# trill-bar.net
KiCad netlist of a schematic drawn in EAGLE
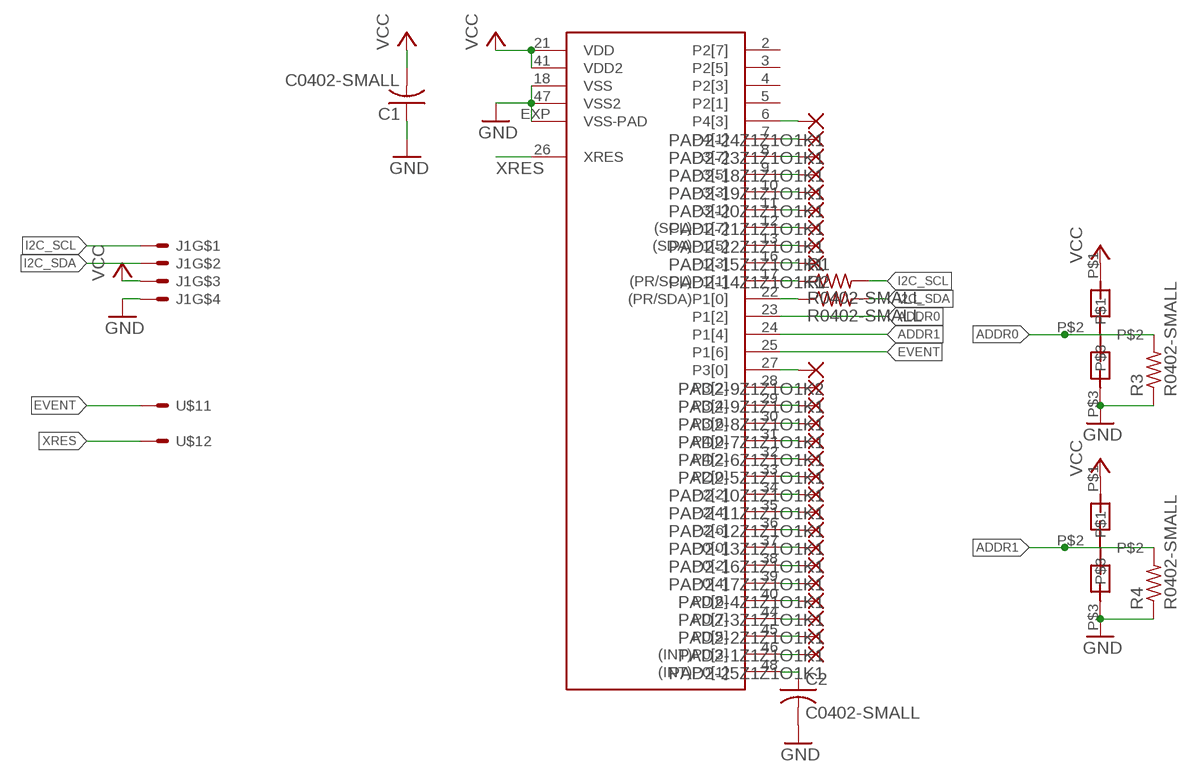
[diagram p0: schematic, sheet 1]

(export (version "E")
  (design (tool "Eeschema 10.0.6"))
  (components
    (comp (ref "C1")
      (value "C0402-SMALL")
      (footprint "eagle-import:C0402-SMALL")
      (libsource (lib "eagle-import") (part "C0402-SMALL"))
    )
    (comp (ref "C2")
      (value "C0402-SMALL")
      (footprint "eagle-import:C0402-SMALL")
      (libsource (lib "eagle-import") (part "C0402-SMALL"))
    )
    (comp (ref "IC1")
      (value "CY8C206X6A")
      (footprint "eagle-import:QFN48-LEADS")
      (libsource (lib "eagle-import") (part "CY8C206X6A"))
    )
    (comp (ref "J1")
      (value "GROVE-SMT")
      (footprint "eagle-import:JST-PH-4-SMT")
      (libsource (lib "eagle-import") (part "GROVE-SMT"))
    )
    (comp (ref "PAD2-1Z1Z1O1K1")
      (value "SMD2")
      (footprint "eagle-import:SMD1,27-2,54")
      (libsource (lib "eagle-import") (part "SMD2"))
    )
    (comp (ref "PAD2-2Z1Z1O1K1")
      (value "SMD2")
      (footprint "eagle-import:SMD1,27-2,54")
      (libsource (lib "eagle-import") (part "SMD2"))
    )
    (comp (ref "PAD2-3Z1Z1O1K1")
      (value "SMD2")
      (footprint "eagle-import:SMD1,27-2,54")
      (libsource (lib "eagle-import") (part "SMD2"))
    )
    (comp (ref "PAD2-4Z1Z1O1K1")
      (value "SMD2")
      (footprint "eagle-import:SMD1,27-2,54")
      (libsource (lib "eagle-import") (part "SMD2"))
    )
    (comp (ref "PAD2-5Z1Z1O1K1")
      (value "SMD2")
      (footprint "eagle-import:SMD1,27-2,54")
      (libsource (lib "eagle-import") (part "SMD2"))
    )
    (comp (ref "PAD2-6Z1Z1O1K1")
      (value "SMD2")
      (footprint "eagle-import:SMD1,27-2,54")
      (libsource (lib "eagle-import") (part "SMD2"))
    )
    (comp (ref "PAD2-7Z1Z1O1K1")
      (value "SMD2")
      (footprint "eagle-import:SMD1,27-2,54")
      (libsource (lib "eagle-import") (part "SMD2"))
    )
    (comp (ref "PAD2-8Z1Z1O1K1")
      (value "SMD2")
      (footprint "eagle-import:SMD1,27-2,54")
      (libsource (lib "eagle-import") (part "SMD2"))
    )
    (comp (ref "PAD2-9Z1Z1O1K1")
      (value "SMD2")
      (footprint "eagle-import:SMD1,27-2,54")
      (libsource (lib "eagle-import") (part "SMD2"))
    )
    (comp (ref "PAD2-9Z1Z1O1K2")
      (value "SMD2")
      (footprint "eagle-import:SMD1,27-2,54")
      (libsource (lib "eagle-import") (part "SMD2"))
    )
    (comp (ref "PAD2-10Z1Z1O1K1")
      (value "SMD2")
      (footprint "eagle-import:SMD1,27-2,54")
      (libsource (lib "eagle-import") (part "SMD2"))
    )
    (comp (ref "PAD2-11Z1Z1O1K1")
      (value "SMD2")
      (footprint "eagle-import:SMD1,27-2,54")
      (libsource (lib "eagle-import") (part "SMD2"))
    )
    (comp (ref "PAD2-12Z1Z1O1K1")
      (value "SMD2")
      (footprint "eagle-import:SMD1,27-2,54")
      (libsource (lib "eagle-import") (part "SMD2"))
    )
    (comp (ref "PAD2-13Z1Z1O1K1")
      (value "SMD2")
      (footprint "eagle-import:SMD1,27-2,54")
      (libsource (lib "eagle-import") (part "SMD2"))
    )
    (comp (ref "PAD2-14Z1Z1O1K1")
      (value "SMD2")
      (footprint "eagle-import:SMD1,27-2,54")
      (libsource (lib "eagle-import") (part "SMD2"))
    )
    (comp (ref "PAD2-15Z1Z1O1K1")
      (value "SMD2")
      (footprint "eagle-import:SMD1,27-2,54")
      (libsource (lib "eagle-import") (part "SMD2"))
    )
    (comp (ref "PAD2-16Z1Z1O1K1")
      (value "SMD2")
      (footprint "eagle-import:SMD1,27-2,54")
      (libsource (lib "eagle-import") (part "SMD2"))
    )
    (comp (ref "PAD2-17Z1Z1O1K1")
      (value "SMD2")
      (footprint "eagle-import:SMD1,27-2,54")
      (libsource (lib "eagle-import") (part "SMD2"))
    )
    (comp (ref "PAD2-18Z1Z1O1K1")
      (value "SMD2")
      (footprint "eagle-import:SMD1,27-2,54")
      (libsource (lib "eagle-import") (part "SMD2"))
    )
    (comp (ref "PAD2-19Z1Z1O1K1")
      (value "SMD2")
      (footprint "eagle-import:SMD1,27-2,54")
      (libsource (lib "eagle-import") (part "SMD2"))
    )
    (comp (ref "PAD2-20Z1Z1O1K1")
      (value "SMD2")
      (footprint "eagle-import:SMD1,27-2,54")
      (libsource (lib "eagle-import") (part "SMD2"))
    )
    (comp (ref "PAD2-21Z1Z1O1K1")
      (value "SMD2")
      (footprint "eagle-import:SMD1,27-2,54")
      (libsource (lib "eagle-import") (part "SMD2"))
    )
    (comp (ref "PAD2-22Z1Z1O1K1")
      (value "SMD2")
      (footprint "eagle-import:SMD1,27-2,54")
      (libsource (lib "eagle-import") (part "SMD2"))
    )
    (comp (ref "PAD2-23Z1Z1O1K1")
      (value "SMD2")
      (footprint "eagle-import:SMD1,27-2,54")
      (libsource (lib "eagle-import") (part "SMD2"))
    )
    (comp (ref "PAD2-24Z1Z1O1K1")
      (value "SMD2")
      (footprint "eagle-import:SMD1,27-2,54")
      (libsource (lib "eagle-import") (part "SMD2"))
    )
    (comp (ref "PAD2-25Z1Z1O1K1")
      (value "SMD2")
      (footprint "eagle-import:SMD1,27-2,54")
      (libsource (lib "eagle-import") (part "SMD2"))
    )
    (comp (ref "R1")
      (value "R0402-SMALL")
      (footprint "eagle-import:C0402-SMALL")
      (libsource (lib "eagle-import") (part "R0402-SMALL"))
    )
    (comp (ref "R2")
      (value "R0402-SMALL")
      (footprint "eagle-import:C0402-SMALL")
      (libsource (lib "eagle-import") (part "R0402-SMALL"))
    )
    (comp (ref "R3")
      (value "R0402-SMALL")
      (footprint "eagle-import:C0402-SMALL")
      (libsource (lib "eagle-import") (part "R0402-SMALL"))
    )
    (comp (ref "R4")
      (value "R0402-SMALL")
      (footprint "eagle-import:C0402-SMALL")
      (libsource (lib "eagle-import") (part "R0402-SMALL"))
    )
    (comp (ref "U$7")
      (value "SOLDER_JUMPER_3PAD")
      (footprint "eagle-import:SOLDER_JUMPER_3PAD")
      (libsource (lib "eagle-import") (part "SOLDER_JUMPER_3PAD"))
    )
    (comp (ref "U$8")
      (value "SOLDER_JUMPER_3PAD")
      (footprint "eagle-import:SOLDER_JUMPER_3PAD")
      (libsource (lib "eagle-import") (part "SOLDER_JUMPER_3PAD"))
    )
    (comp (ref "U$11")
      (value "JST-SMT-EXTRAPAD")
      (footprint "eagle-import:JST-SMT-EXTRAPAD")
      (libsource (lib "eagle-import") (part "JST-SMT-EXTRAPAD"))
    )
    (comp (ref "U$12")
      (value "JST-SMT-EXTRAPAD")
      (footprint "eagle-import:JST-SMT-EXTRAPAD")
      (libsource (lib "eagle-import") (part "JST-SMT-EXTRAPAD"))
    )
  )
  (nets
    (net (code "1") (name "ADDR0") (class "Default")
      (node (ref "IC1") (pin "23") (pinfunction "P1[2]_23") (pintype "bidirectional"))
      (node (ref "R3") (pin "P$2") (pinfunction "2_P$2") (pintype "passive"))
      (node (ref "U$7") (pin "P$2") (pinfunction "P$2_P$2") (pintype "bidirectional"))
    )
    (net (code "2") (name "ADDR1") (class "Default")
      (node (ref "IC1") (pin "24") (pinfunction "P1[4]_24") (pintype "bidirectional"))
      (node (ref "R4") (pin "P$2") (pinfunction "2_P$2") (pintype "passive"))
      (node (ref "U$8") (pin "P$2") (pinfunction "P$2_P$2") (pintype "bidirectional"))
    )
    (net (code "3") (name "EVENT") (class "Default")
      (node (ref "IC1") (pin "25") (pinfunction "P1[6]_25") (pintype "bidirectional"))
      (node (ref "U$11") (pin "P$1") (pinfunction "S_P$1") (pintype "passive"))
    )
    (net (code "4") (name "GND") (class "Default")
      (node (ref "C1") (pin "P$1") (pinfunction "1_P$1") (pintype "passive"))
      (node (ref "C2") (pin "P$2") (pinfunction "2_P$2") (pintype "passive"))
      (node (ref "IC1") (pin "18") (pinfunction "VSS_18") (pintype "bidirectional"))
      (node (ref "IC1") (pin "47") (pinfunction "VSS2_47") (pintype "bidirectional"))
      (node (ref "IC1") (pin "EXP") (pinfunction "VSS-PAD_EXP") (pintype "bidirectional"))
      (node (ref "J1") (pin "4") (pinfunction "S_4") (pintype "passive"))
      (node (ref "R3") (pin "P$1") (pinfunction "1_P$1") (pintype "passive"))
      (node (ref "R4") (pin "P$1") (pinfunction "1_P$1") (pintype "passive"))
      (node (ref "U$7") (pin "P$3") (pinfunction "P$3_P$3") (pintype "bidirectional"))
      (node (ref "U$8") (pin "P$3") (pinfunction "P$3_P$3") (pintype "bidirectional"))
    )
    (net (code "5") (name "I2C_SCL") (class "Default")
      (node (ref "J1") (pin "1") (pinfunction "S_1") (pintype "passive"))
      (node (ref "R1") (pin "P$2") (pinfunction "2_P$2") (pintype "passive"))
    )
    (net (code "6") (name "I2C_SDA") (class "Default")
      (node (ref "J1") (pin "2") (pinfunction "S_2") (pintype "passive"))
      (node (ref "R2") (pin "P$2") (pinfunction "2_P$2") (pintype "passive"))
    )
    (net (code "7") (name "Net-(C2-1)") (class "Default")
      (node (ref "C2") (pin "P$1") (pinfunction "1_P$1") (pintype "passive"))
      (node (ref "IC1") (pin "48") (pinfunction "(INT)P0[1]_48") (pintype "bidirectional"))
    )
    (net (code "8") (name "Net-(IC1-(INT)P0[3])") (class "Default")
      (node (ref "IC1") (pin "46") (pinfunction "(INT)P0[3]_46") (pintype "bidirectional"))
      (node (ref "PAD2-25Z1Z1O1K1") (pin "1") (pinfunction "P_1") (pintype "passive"))
    )
    (net (code "9") (name "Net-(IC1-(PR{slash}SCL)P1[1])") (class "Default")
      (node (ref "IC1") (pin "17") (pinfunction "(PR/SCL)P1[1]_17") (pintype "bidirectional"))
      (node (ref "R1") (pin "P$1") (pinfunction "1_P$1") (pintype "passive"))
    )
    (net (code "10") (name "Net-(IC1-(PR{slash}SDA)P1[0])") (class "Default")
      (node (ref "IC1") (pin "22") (pinfunction "(PR/SDA)P1[0]_22") (pintype "bidirectional"))
      (node (ref "R2") (pin "P$1") (pinfunction "1_P$1") (pintype "passive"))
    )
    (net (code "11") (name "Net-(IC1-(SCL)P1[7])") (class "Default")
      (node (ref "IC1") (pin "12") (pinfunction "(SCL)P1[7]_12") (pintype "bidirectional"))
      (node (ref "PAD2-22Z1Z1O1K1") (pin "1") (pinfunction "P_1") (pintype "passive"))
    )
    (net (code "12") (name "Net-(IC1-(SDA)P1[5])") (class "Default")
      (node (ref "IC1") (pin "13") (pinfunction "(SDA)P1[5]_13") (pintype "bidirectional"))
      (node (ref "PAD2-15Z1Z1O1K1") (pin "1") (pinfunction "P_1") (pintype "passive"))
    )
    (net (code "13") (name "Net-(IC1-P0[0])") (class "Default")
      (node (ref "IC1") (pin "37") (pinfunction "P0[0]_37") (pintype "bidirectional"))
      (node (ref "PAD2-16Z1Z1O1K1") (pin "1") (pinfunction "P_1") (pintype "passive"))
    )
    (net (code "14") (name "Net-(IC1-P0[2])") (class "Default")
      (node (ref "IC1") (pin "38") (pinfunction "P0[2]_38") (pintype "bidirectional"))
      (node (ref "PAD2-17Z1Z1O1K1") (pin "1") (pinfunction "P_1") (pintype "passive"))
    )
    (net (code "15") (name "Net-(IC1-P0[4])") (class "Default")
      (node (ref "IC1") (pin "39") (pinfunction "P0[4]_39") (pintype "bidirectional"))
      (node (ref "PAD2-4Z1Z1O1K1") (pin "1") (pinfunction "P_1") (pintype "passive"))
    )
    (net (code "16") (name "Net-(IC1-P0[5])") (class "Default")
      (node (ref "IC1") (pin "45") (pinfunction "P0[5]_45") (pintype "bidirectional"))
      (node (ref "PAD2-1Z1Z1O1K1") (pin "1") (pinfunction "P_1") (pintype "passive"))
    )
    (net (code "17") (name "Net-(IC1-P0[6])") (class "Default")
      (node (ref "IC1") (pin "40") (pinfunction "P0[6]_40") (pintype "bidirectional"))
      (node (ref "PAD2-3Z1Z1O1K1") (pin "1") (pinfunction "P_1") (pintype "passive"))
    )
    (net (code "18") (name "Net-(IC1-P0[7])") (class "Default")
      (node (ref "IC1") (pin "44") (pinfunction "P0[7]_44") (pintype "bidirectional"))
      (node (ref "PAD2-2Z1Z1O1K1") (pin "1") (pinfunction "P_1") (pintype "passive"))
    )
    (net (code "19") (name "Net-(IC1-P1[3])") (class "Default")
      (node (ref "IC1") (pin "16") (pinfunction "P1[3]_16") (pintype "bidirectional"))
      (node (ref "PAD2-14Z1Z1O1K1") (pin "1") (pinfunction "P_1") (pintype "passive"))
    )
    (net (code "20") (name "Net-(IC1-P2[0])") (class "Default")
      (node (ref "IC1") (pin "33") (pinfunction "P2[0]_33") (pintype "bidirectional"))
      (node (ref "PAD2-10Z1Z1O1K1") (pin "1") (pinfunction "P_1") (pintype "passive"))
    )
    (net (code "21") (name "Net-(IC1-P2[2])") (class "Default")
      (node (ref "IC1") (pin "34") (pinfunction "P2[2]_34") (pintype "bidirectional"))
      (node (ref "PAD2-11Z1Z1O1K1") (pin "1") (pinfunction "P_1") (pintype "passive"))
    )
    (net (code "22") (name "Net-(IC1-P2[4])") (class "Default")
      (node (ref "IC1") (pin "35") (pinfunction "P2[4]_35") (pintype "bidirectional"))
      (node (ref "PAD2-12Z1Z1O1K1") (pin "1") (pinfunction "P_1") (pintype "passive"))
    )
    (net (code "23") (name "Net-(IC1-P2[6])") (class "Default")
      (node (ref "IC1") (pin "36") (pinfunction "P2[6]_36") (pintype "bidirectional"))
      (node (ref "PAD2-13Z1Z1O1K1") (pin "1") (pinfunction "P_1") (pintype "passive"))
    )
    (net (code "24") (name "Net-(IC1-P3[0])") (class "Default")
      (node (ref "IC1") (pin "27") (pinfunction "P3[0]_27") (pintype "bidirectional"))
      (node (ref "PAD2-9Z1Z1O1K2") (pin "1") (pinfunction "P_1") (pintype "passive"))
    )
    (net (code "25") (name "Net-(IC1-P3[1])") (class "Default")
      (node (ref "IC1") (pin "11") (pinfunction "P3[1]_11") (pintype "bidirectional"))
      (node (ref "PAD2-21Z1Z1O1K1") (pin "1") (pinfunction "P_1") (pintype "passive"))
    )
    (net (code "26") (name "Net-(IC1-P3[2])") (class "Default")
      (node (ref "IC1") (pin "28") (pinfunction "P3[2]_28") (pintype "bidirectional"))
      (node (ref "PAD2-9Z1Z1O1K1") (pin "1") (pinfunction "P_1") (pintype "passive"))
    )
    (net (code "27") (name "Net-(IC1-P3[3])") (class "Default")
      (node (ref "IC1") (pin "10") (pinfunction "P3[3]_10") (pintype "bidirectional"))
      (node (ref "PAD2-20Z1Z1O1K1") (pin "1") (pinfunction "P_1") (pintype "passive"))
    )
    (net (code "28") (name "Net-(IC1-P3[4])") (class "Default")
      (node (ref "IC1") (pin "29") (pinfunction "P3[4]_29") (pintype "bidirectional"))
      (node (ref "PAD2-8Z1Z1O1K1") (pin "1") (pinfunction "P_1") (pintype "passive"))
    )
    (net (code "29") (name "Net-(IC1-P3[5])") (class "Default")
      (node (ref "IC1") (pin "9") (pinfunction "P3[5]_9") (pintype "bidirectional"))
      (node (ref "PAD2-19Z1Z1O1K1") (pin "1") (pinfunction "P_1") (pintype "passive"))
    )
    (net (code "30") (name "Net-(IC1-P3[6])") (class "Default")
      (node (ref "IC1") (pin "30") (pinfunction "P3[6]_30") (pintype "bidirectional"))
      (node (ref "PAD2-7Z1Z1O1K1") (pin "1") (pinfunction "P_1") (pintype "passive"))
    )
    (net (code "31") (name "Net-(IC1-P3[7])") (class "Default")
      (node (ref "IC1") (pin "8") (pinfunction "P3[7]_8") (pintype "bidirectional"))
      (node (ref "PAD2-18Z1Z1O1K1") (pin "1") (pinfunction "P_1") (pintype "passive"))
    )
    (net (code "32") (name "Net-(IC1-P4[0])") (class "Default")
      (node (ref "IC1") (pin "31") (pinfunction "P4[0]_31") (pintype "bidirectional"))
      (node (ref "PAD2-6Z1Z1O1K1") (pin "1") (pinfunction "P_1") (pintype "passive"))
    )
    (net (code "33") (name "Net-(IC1-P4[1])") (class "Default")
      (node (ref "IC1") (pin "7") (pinfunction "P4[1]_7") (pintype "bidirectional"))
      (node (ref "PAD2-23Z1Z1O1K1") (pin "1") (pinfunction "P_1") (pintype "passive"))
    )
    (net (code "34") (name "Net-(IC1-P4[2])") (class "Default")
      (node (ref "IC1") (pin "32") (pinfunction "P4[2]_32") (pintype "bidirectional"))
      (node (ref "PAD2-5Z1Z1O1K1") (pin "1") (pinfunction "P_1") (pintype "passive"))
    )
    (net (code "35") (name "Net-(IC1-P4[3])") (class "Default")
      (node (ref "IC1") (pin "6") (pinfunction "P4[3]_6") (pintype "bidirectional"))
      (node (ref "PAD2-24Z1Z1O1K1") (pin "1") (pinfunction "P_1") (pintype "passive"))
    )
    (net (code "36") (name "VCC") (class "Default")
      (node (ref "C1") (pin "P$2") (pinfunction "2_P$2") (pintype "passive"))
      (node (ref "IC1") (pin "21") (pinfunction "VDD_21") (pintype "bidirectional"))
      (node (ref "IC1") (pin "41") (pinfunction "VDD2_41") (pintype "bidirectional"))
      (node (ref "J1") (pin "3") (pinfunction "S_3") (pintype "passive"))
      (node (ref "U$7") (pin "P$1") (pinfunction "P$1_P$1") (pintype "bidirectional"))
      (node (ref "U$8") (pin "P$1") (pinfunction "P$1_P$1") (pintype "bidirectional"))
    )
    (net (code "37") (name "XRES") (class "Default")
      (node (ref "IC1") (pin "26") (pinfunction "XRES_26") (pintype "bidirectional"))
      (node (ref "U$12") (pin "P$1") (pinfunction "S_P$1") (pintype "passive"))
    )
    (net (code "38") (name "unconnected-(IC1-P2[1]-Pad5)") (class "Default")
      (node (ref "IC1") (pin "5") (pinfunction "P2[1]_5") (pintype "bidirectional"))
    )
    (net (code "39") (name "unconnected-(IC1-P2[3]-Pad4)") (class "Default")
      (node (ref "IC1") (pin "4") (pinfunction "P2[3]_4") (pintype "bidirectional"))
    )
    (net (code "40") (name "unconnected-(IC1-P2[5]-Pad3)") (class "Default")
      (node (ref "IC1") (pin "3") (pinfunction "P2[5]_3") (pintype "bidirectional"))
    )
    (net (code "41") (name "unconnected-(IC1-P2[7]-Pad2)") (class "Default")
      (node (ref "IC1") (pin "2") (pinfunction "P2[7]_2") (pintype "bidirectional"))
    )
  )
)
